# imu.net
KiCad netlist of a schematic drawn in EAGLE
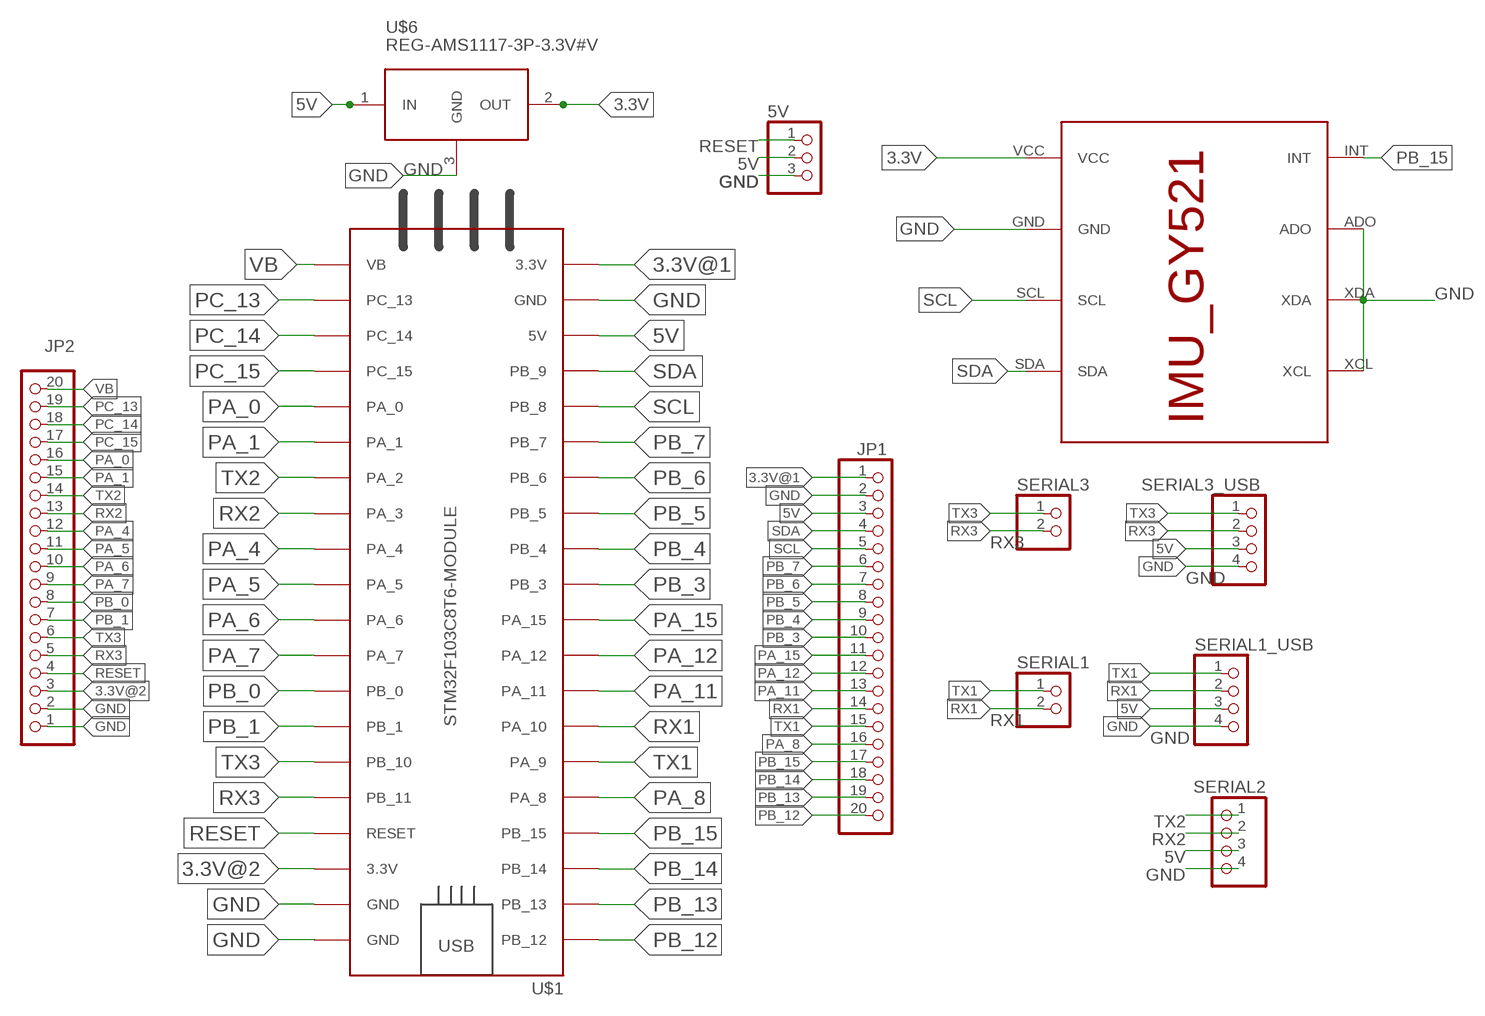
[diagram p0: schematic, sheet 1]

(export (version "E")
  (design (tool "Eeschema 10.0.6"))
  (components
    (comp (ref "5V")
      (value "PINHD-3_DATA")
      (footprint "eagle-import:1X03_DATA")
      (libsource (lib "eagle-import") (part "PINHD-3_DATA"))
    )
    (comp (ref "JP1")
      (value "PINHD-1X20")
      (footprint "eagle-import:1X20")
      (libsource (lib "eagle-import") (part "PINHD-1X20"))
    )
    (comp (ref "JP2")
      (value "PINHD-1X20")
      (footprint "eagle-import:1X20")
      (libsource (lib "eagle-import") (part "PINHD-1X20"))
    )
    (comp (ref "SERIAL1")
      (value "PINHD-2_DATA")
      (footprint "eagle-import:1X02_DATA")
      (libsource (lib "eagle-import") (part "PINHD-2_DATA"))
    )
    (comp (ref "SERIAL1_USB")
      (value "PINHD-4_DATA")
      (footprint "eagle-import:1X04_DATA")
      (libsource (lib "eagle-import") (part "PINHD-4_DATA"))
    )
    (comp (ref "SERIAL2")
      (value "PINHD-4_DATA")
      (footprint "eagle-import:1X04_DATA")
      (libsource (lib "eagle-import") (part "PINHD-4_DATA"))
    )
    (comp (ref "SERIAL3")
      (value "PINHD-2_DATA")
      (footprint "eagle-import:1X02_DATA")
      (libsource (lib "eagle-import") (part "PINHD-2_DATA"))
    )
    (comp (ref "SERIAL3_USB")
      (value "PINHD-4_DATA")
      (footprint "eagle-import:1X04_DATA")
      (libsource (lib "eagle-import") (part "PINHD-4_DATA"))
    )
    (comp (ref "U$1")
      (value "STM32F103C8T6-MODULE")
      (footprint "eagle-import:STM32F103C8T6-MODULE")
      (libsource (lib "eagle-import") (part "STM32F103C8T6-MODULE"))
    )
    (comp (ref "U$2")
      (value "IMU_ROBOCON_GY521")
      (footprint "eagle-import:IMU_GY521")
      (libsource (lib "eagle-import") (part "IMU_ROBOCON_GY521"))
    )
    (comp (ref "U$6")
      (value "REG-AMS1117-3P-3.3V#V")
      (footprint "eagle-import:REG-AMS1117-3P#V")
      (libsource (lib "eagle-import") (part "REG-AMS1117-3P-#V3.3V"))
    )
  )
  (nets
    (net (code "1") (name "3.3V") (class "Default")
      (node (ref "U$2") (pin "VCC") (pinfunction "VCC_VCC") (pintype "bidirectional"))
      (node (ref "U$6") (pin "2") (pinfunction "OUT_2") (pintype "bidirectional"))
    )
    (net (code "2") (name "3.3V@1") (class "Default")
      (node (ref "JP1") (pin "1") (pinfunction "1_1") (pintype "passive"))
      (node (ref "U$1") (pin "3.3V_1") (pinfunction "3.3V_3.3V_1") (pintype "bidirectional"))
    )
    (net (code "3") (name "3.3V@2") (class "Default")
      (node (ref "JP2") (pin "3") (pinfunction "3_3") (pintype "passive"))
      (node (ref "U$1") (pin "3.3V_2") (pinfunction "3.3V_3.3V_2") (pintype "bidirectional"))
    )
    (net (code "4") (name "5V") (class "Default")
      (node (ref "5V") (pin "2") (pinfunction "2_2") (pintype "passive"))
      (node (ref "JP1") (pin "3") (pinfunction "3_3") (pintype "passive"))
      (node (ref "SERIAL1_USB") (pin "3") (pinfunction "3_3") (pintype "passive"))
      (node (ref "SERIAL2") (pin "3") (pinfunction "3_3") (pintype "passive"))
      (node (ref "SERIAL3_USB") (pin "3") (pinfunction "3_3") (pintype "passive"))
      (node (ref "U$1") (pin "5V") (pinfunction "5V_5V") (pintype "bidirectional"))
      (node (ref "U$6") (pin "1") (pinfunction "IN_1") (pintype "bidirectional"))
    )
    (net (code "5") (name "GND") (class "Default")
      (node (ref "5V") (pin "3") (pinfunction "3_3") (pintype "passive"))
      (node (ref "JP1") (pin "2") (pinfunction "2_2") (pintype "passive"))
      (node (ref "JP2") (pin "1") (pinfunction "1_1") (pintype "passive"))
      (node (ref "JP2") (pin "2") (pinfunction "2_2") (pintype "passive"))
      (node (ref "SERIAL1_USB") (pin "4") (pinfunction "4_4") (pintype "passive"))
      (node (ref "SERIAL2") (pin "4") (pinfunction "4_4") (pintype "passive"))
      (node (ref "SERIAL3_USB") (pin "4") (pinfunction "4_4") (pintype "passive"))
      (node (ref "U$1") (pin "GND_1") (pinfunction "GND_GND_1") (pintype "bidirectional"))
      (node (ref "U$1") (pin "GND_2") (pinfunction "GND_GND_2") (pintype "bidirectional"))
      (node (ref "U$1") (pin "GND_3") (pinfunction "GND_GND_3") (pintype "power_in"))
      (node (ref "U$2") (pin "ADO") (pinfunction "ADO_ADO") (pintype "bidirectional"))
      (node (ref "U$2") (pin "GND") (pinfunction "GND_GND") (pintype "bidirectional"))
      (node (ref "U$2") (pin "XCL") (pinfunction "XCL_XCL") (pintype "bidirectional"))
      (node (ref "U$2") (pin "XDA") (pinfunction "XDA_XDA") (pintype "bidirectional"))
      (node (ref "U$6") (pin "3") (pinfunction "GND_3") (pintype "bidirectional"))
    )
    (net (code "6") (name "PA_0") (class "Default")
      (node (ref "JP2") (pin "16") (pinfunction "16_16") (pintype "passive"))
      (node (ref "U$1") (pin "PA_0") (pinfunction "PA_0_PA_0") (pintype "bidirectional"))
    )
    (net (code "7") (name "PA_1") (class "Default")
      (node (ref "JP2") (pin "15") (pinfunction "15_15") (pintype "passive"))
      (node (ref "U$1") (pin "PA_1") (pinfunction "PA_1_PA_1") (pintype "bidirectional"))
    )
    (net (code "8") (name "PA_4") (class "Default")
      (node (ref "JP2") (pin "12") (pinfunction "12_12") (pintype "passive"))
      (node (ref "U$1") (pin "PA_4") (pinfunction "PA_4_PA_4") (pintype "bidirectional"))
    )
    (net (code "9") (name "PA_5") (class "Default")
      (node (ref "JP2") (pin "11") (pinfunction "11_11") (pintype "passive"))
      (node (ref "U$1") (pin "PA_5") (pinfunction "PA_5_PA_5") (pintype "bidirectional"))
    )
    (net (code "10") (name "PA_6") (class "Default")
      (node (ref "JP2") (pin "10") (pinfunction "10_10") (pintype "passive"))
      (node (ref "U$1") (pin "PA_6") (pinfunction "PA_6_PA_6") (pintype "bidirectional"))
    )
    (net (code "11") (name "PA_7") (class "Default")
      (node (ref "JP2") (pin "9") (pinfunction "9_9") (pintype "passive"))
      (node (ref "U$1") (pin "PA_7") (pinfunction "PA_7_PA_7") (pintype "bidirectional"))
    )
    (net (code "12") (name "PA_8") (class "Default")
      (node (ref "JP1") (pin "16") (pinfunction "16_16") (pintype "passive"))
      (node (ref "U$1") (pin "PA_8") (pinfunction "PA_8_PA_8") (pintype "bidirectional"))
    )
    (net (code "13") (name "PA_11") (class "Default")
      (node (ref "JP1") (pin "13") (pinfunction "13_13") (pintype "passive"))
      (node (ref "U$1") (pin "PA_11") (pinfunction "PA_11_PA_11") (pintype "bidirectional"))
    )
    (net (code "14") (name "PA_12") (class "Default")
      (node (ref "JP1") (pin "12") (pinfunction "12_12") (pintype "passive"))
      (node (ref "U$1") (pin "PA_12") (pinfunction "PA_12_PA_12") (pintype "bidirectional"))
    )
    (net (code "15") (name "PA_15") (class "Default")
      (node (ref "JP1") (pin "11") (pinfunction "11_11") (pintype "passive"))
      (node (ref "U$1") (pin "PA_15") (pinfunction "PA_15_PA_15") (pintype "bidirectional"))
    )
    (net (code "16") (name "PB_0") (class "Default")
      (node (ref "JP2") (pin "8") (pinfunction "8_8") (pintype "passive"))
      (node (ref "U$1") (pin "PB_0") (pinfunction "PB_0_PB_0") (pintype "bidirectional"))
    )
    (net (code "17") (name "PB_1") (class "Default")
      (node (ref "JP2") (pin "7") (pinfunction "7_7") (pintype "passive"))
      (node (ref "U$1") (pin "PB_1") (pinfunction "PB_1_PB_1") (pintype "bidirectional"))
    )
    (net (code "18") (name "PB_3") (class "Default")
      (node (ref "JP1") (pin "10") (pinfunction "10_10") (pintype "passive"))
      (node (ref "U$1") (pin "PB_3") (pinfunction "PB_3_PB_3") (pintype "bidirectional"))
    )
    (net (code "19") (name "PB_4") (class "Default")
      (node (ref "JP1") (pin "9") (pinfunction "9_9") (pintype "passive"))
      (node (ref "U$1") (pin "PB_4") (pinfunction "PB_4_PB_4") (pintype "bidirectional"))
    )
    (net (code "20") (name "PB_5") (class "Default")
      (node (ref "JP1") (pin "8") (pinfunction "8_8") (pintype "passive"))
      (node (ref "U$1") (pin "PB_5") (pinfunction "PB_5_PB_5") (pintype "bidirectional"))
    )
    (net (code "21") (name "PB_6") (class "Default")
      (node (ref "JP1") (pin "7") (pinfunction "7_7") (pintype "passive"))
      (node (ref "U$1") (pin "PB_6") (pinfunction "PB_6_PB_6") (pintype "bidirectional"))
    )
    (net (code "22") (name "PB_7") (class "Default")
      (node (ref "JP1") (pin "6") (pinfunction "6_6") (pintype "passive"))
      (node (ref "U$1") (pin "PB_7") (pinfunction "PB_7_PB_7") (pintype "bidirectional"))
    )
    (net (code "23") (name "PB_12") (class "Default")
      (node (ref "JP1") (pin "20") (pinfunction "20_20") (pintype "passive"))
      (node (ref "U$1") (pin "PB_12") (pinfunction "PB_12_PB_12") (pintype "bidirectional"))
    )
    (net (code "24") (name "PB_13") (class "Default")
      (node (ref "JP1") (pin "19") (pinfunction "19_19") (pintype "passive"))
      (node (ref "U$1") (pin "PB_13") (pinfunction "PB_13_PB_13") (pintype "bidirectional"))
    )
    (net (code "25") (name "PB_14") (class "Default")
      (node (ref "JP1") (pin "18") (pinfunction "18_18") (pintype "passive"))
      (node (ref "U$1") (pin "PB_14") (pinfunction "PB_14_PB_14") (pintype "bidirectional"))
    )
    (net (code "26") (name "PB_15") (class "Default")
      (node (ref "JP1") (pin "17") (pinfunction "17_17") (pintype "passive"))
      (node (ref "U$1") (pin "PB_15") (pinfunction "PB_15_PB_15") (pintype "bidirectional"))
      (node (ref "U$2") (pin "INT") (pinfunction "INT_INT") (pintype "bidirectional"))
    )
    (net (code "27") (name "PC_13") (class "Default")
      (node (ref "JP2") (pin "19") (pinfunction "19_19") (pintype "passive"))
      (node (ref "U$1") (pin "PC_13") (pinfunction "PC_13_PC_13") (pintype "bidirectional"))
    )
    (net (code "28") (name "PC_14") (class "Default")
      (node (ref "JP2") (pin "18") (pinfunction "18_18") (pintype "passive"))
      (node (ref "U$1") (pin "PC_14") (pinfunction "PC_14_PC_14") (pintype "bidirectional"))
    )
    (net (code "29") (name "PC_15") (class "Default")
      (node (ref "JP2") (pin "17") (pinfunction "17_17") (pintype "passive"))
      (node (ref "U$1") (pin "PC_15") (pinfunction "PC_15_PC_15") (pintype "bidirectional"))
    )
    (net (code "30") (name "RESET") (class "Default")
      (node (ref "5V") (pin "1") (pinfunction "1_1") (pintype "passive"))
      (node (ref "JP2") (pin "4") (pinfunction "4_4") (pintype "passive"))
      (node (ref "U$1") (pin "RESET") (pinfunction "RESET_RESET") (pintype "bidirectional"))
    )
    (net (code "31") (name "RX1") (class "Default")
      (node (ref "JP1") (pin "14") (pinfunction "14_14") (pintype "passive"))
      (node (ref "SERIAL1") (pin "2") (pinfunction "2_2") (pintype "passive"))
      (node (ref "SERIAL1_USB") (pin "2") (pinfunction "2_2") (pintype "passive"))
      (node (ref "U$1") (pin "PA_10") (pinfunction "PA_10_PA_10") (pintype "bidirectional"))
    )
    (net (code "32") (name "RX2") (class "Default")
      (node (ref "JP2") (pin "13") (pinfunction "13_13") (pintype "passive"))
      (node (ref "SERIAL2") (pin "2") (pinfunction "2_2") (pintype "passive"))
      (node (ref "U$1") (pin "PA_3") (pinfunction "PA_3_PA_3") (pintype "bidirectional"))
    )
    (net (code "33") (name "RX3") (class "Default")
      (node (ref "JP2") (pin "5") (pinfunction "5_5") (pintype "passive"))
      (node (ref "SERIAL3") (pin "2") (pinfunction "2_2") (pintype "passive"))
      (node (ref "SERIAL3_USB") (pin "2") (pinfunction "2_2") (pintype "passive"))
      (node (ref "U$1") (pin "PB_11") (pinfunction "PB_11_PB_11") (pintype "bidirectional"))
    )
    (net (code "34") (name "SCL") (class "Default")
      (node (ref "JP1") (pin "5") (pinfunction "5_5") (pintype "passive"))
      (node (ref "U$1") (pin "PB_8") (pinfunction "PB_8_PB_8") (pintype "bidirectional"))
      (node (ref "U$2") (pin "SCL") (pinfunction "SCL_SCL") (pintype "bidirectional"))
    )
    (net (code "35") (name "SDA") (class "Default")
      (node (ref "JP1") (pin "4") (pinfunction "4_4") (pintype "passive"))
      (node (ref "U$1") (pin "PB_9") (pinfunction "PB_9_PB_9") (pintype "bidirectional"))
      (node (ref "U$2") (pin "SDA") (pinfunction "SDA_SDA") (pintype "bidirectional"))
    )
    (net (code "36") (name "TX1") (class "Default")
      (node (ref "JP1") (pin "15") (pinfunction "15_15") (pintype "passive"))
      (node (ref "SERIAL1") (pin "1") (pinfunction "1_1") (pintype "passive"))
      (node (ref "SERIAL1_USB") (pin "1") (pinfunction "1_1") (pintype "passive"))
      (node (ref "U$1") (pin "PA_9") (pinfunction "PA_9_PA_9") (pintype "bidirectional"))
    )
    (net (code "37") (name "TX2") (class "Default")
      (node (ref "JP2") (pin "14") (pinfunction "14_14") (pintype "passive"))
      (node (ref "SERIAL2") (pin "1") (pinfunction "1_1") (pintype "passive"))
      (node (ref "U$1") (pin "PA_2") (pinfunction "PA_2_PA_2") (pintype "bidirectional"))
    )
    (net (code "38") (name "TX3") (class "Default")
      (node (ref "JP2") (pin "6") (pinfunction "6_6") (pintype "passive"))
      (node (ref "SERIAL3") (pin "1") (pinfunction "1_1") (pintype "passive"))
      (node (ref "SERIAL3_USB") (pin "1") (pinfunction "1_1") (pintype "passive"))
      (node (ref "U$1") (pin "PB_10") (pinfunction "PB_10_PB_10") (pintype "bidirectional"))
    )
    (net (code "39") (name "VB") (class "Default")
      (node (ref "JP2") (pin "20") (pinfunction "20_20") (pintype "passive"))
      (node (ref "U$1") (pin "VB") (pinfunction "VB_VB") (pintype "bidirectional"))
    )
  )
)
